# Antenna_Board.net
KiCad netlist of a schematic drawn in EAGLE
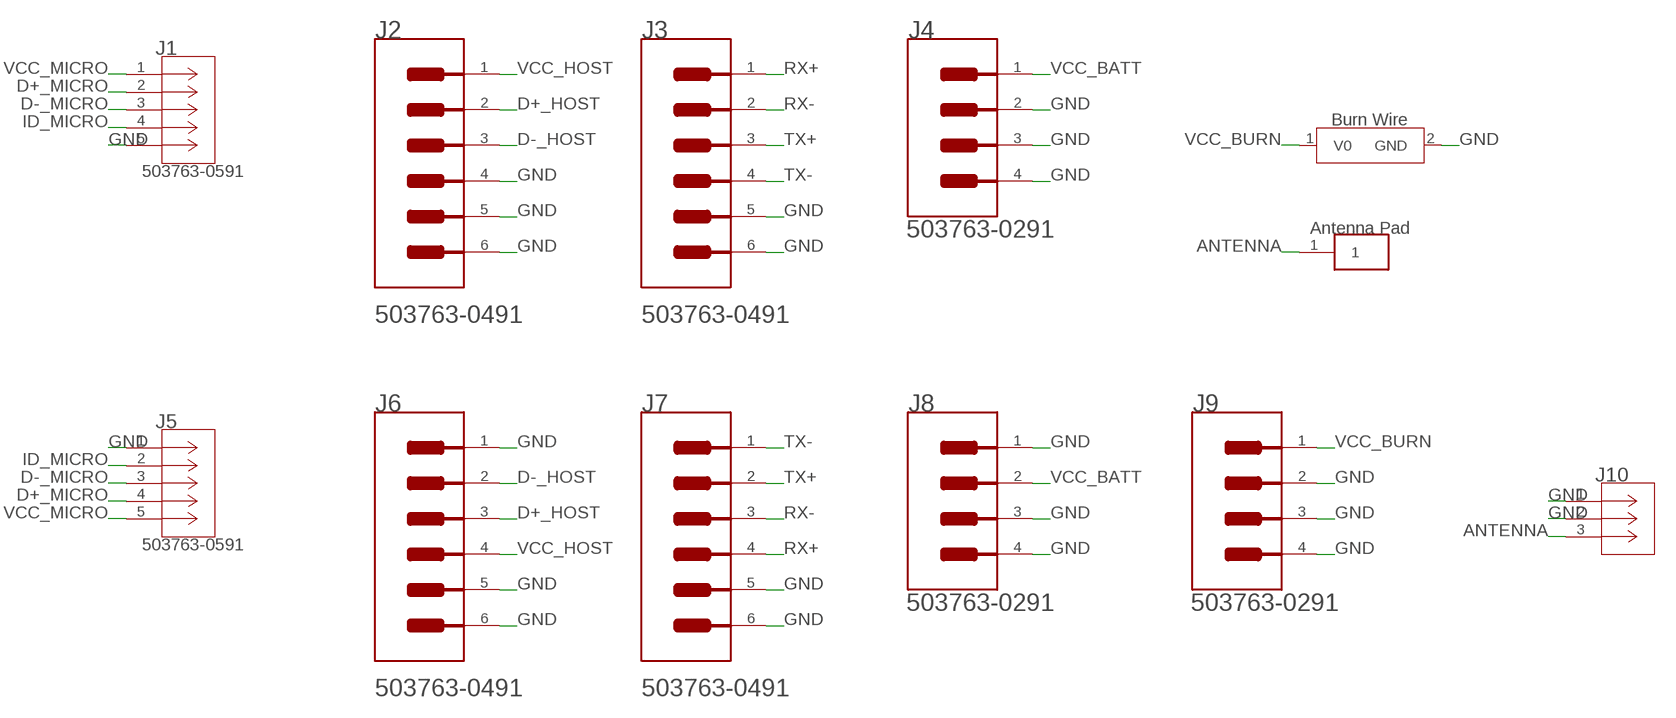
[diagram p0: schematic, sheet 1]

(export (version "E")
  (design (tool "Eeschema 10.0.6"))
  (components
    (comp (ref "J1")
      (value "503763-0591")
      (footprint "eagle-import:CONN_5037630591_MOL")
      (fields (field (name "COPYRIGHT") "Copyright (C) 2018 Accelerated Designs. All rights reserved"))
      (libsource (lib "eagle-import") (part "503763-0591"))
    )
    (comp (ref "J2")
      (value "MOLEX_503763-0491MOLEX_503763-0491_0_0")
      (footprint "eagle-import:MOLEX_503763-0491_0")
      (fields
        (field (name "DIGIKEY_PART_NUMBER") "WM10655CT-ND")
        (field (name "MF") "Molex")
        (field (name "MOUSER_PART_NUMBER") "538-503763-0491")
      )
      (libsource (lib "eagle-import") (part "MOLEX_503763-0491MOLEX_503763-0491_0_0"))
    )
    (comp (ref "J3")
      (value "MOLEX_503763-0491MOLEX_503763-0491_0_0")
      (footprint "eagle-import:MOLEX_503763-0491_0")
      (fields
        (field (name "DIGIKEY_PART_NUMBER") "WM10655CT-ND")
        (field (name "MF") "Molex")
        (field (name "MOUSER_PART_NUMBER") "538-503763-0491")
      )
      (libsource (lib "eagle-import") (part "MOLEX_503763-0491MOLEX_503763-0491_0_0"))
    )
    (comp (ref "J4")
      (value "MOLEX_503763-0291MOLEX_503763-0291_0_0")
      (footprint "eagle-import:MOLEX_503763-0291_0")
      (fields
        (field (name "DIGIKEY_PART_NUMBER") "WM10654CT-ND")
        (field (name "MF") "Molex")
        (field (name "MOUSER_PART_NUMBER") "538-503763-0291")
      )
      (libsource (lib "eagle-import") (part "MOLEX_503763-0291MOLEX_503763-0291_0_0"))
    )
    (comp (ref "J5")
      (value "503763-0591")
      (footprint "eagle-import:CONN_5037630591_MOL")
      (fields (field (name "COPYRIGHT") "Copyright (C) 2018 Accelerated Designs. All rights reserved"))
      (libsource (lib "eagle-import") (part "503763-0591"))
    )
    (comp (ref "J6")
      (value "MOLEX_503763-0491MOLEX_503763-0491_0_0")
      (footprint "eagle-import:MOLEX_503763-0491_0")
      (fields
        (field (name "DIGIKEY_PART_NUMBER") "WM10655CT-ND")
        (field (name "MF") "Molex")
        (field (name "MOUSER_PART_NUMBER") "538-503763-0491")
      )
      (libsource (lib "eagle-import") (part "MOLEX_503763-0491MOLEX_503763-0491_0_0"))
    )
    (comp (ref "J7")
      (value "MOLEX_503763-0491MOLEX_503763-0491_0_0")
      (footprint "eagle-import:MOLEX_503763-0491_0")
      (fields
        (field (name "DIGIKEY_PART_NUMBER") "WM10655CT-ND")
        (field (name "MF") "Molex")
        (field (name "MOUSER_PART_NUMBER") "538-503763-0491")
      )
      (libsource (lib "eagle-import") (part "MOLEX_503763-0491MOLEX_503763-0491_0_0"))
    )
    (comp (ref "J8")
      (value "MOLEX_503763-0291MOLEX_503763-0291_0_0")
      (footprint "eagle-import:MOLEX_503763-0291_0")
      (fields
        (field (name "DIGIKEY_PART_NUMBER") "WM10654CT-ND")
        (field (name "MF") "Molex")
        (field (name "MOUSER_PART_NUMBER") "538-503763-0291")
      )
      (libsource (lib "eagle-import") (part "MOLEX_503763-0291MOLEX_503763-0291_0_0"))
    )
    (comp (ref "J9")
      (value "MOLEX_503763-0291MOLEX_503763-0291_0_0")
      (footprint "eagle-import:MOLEX_503763-0291_0")
      (fields
        (field (name "DIGIKEY_PART_NUMBER") "WM10654CT-ND")
        (field (name "MF") "Molex")
        (field (name "MOUSER_PART_NUMBER") "538-503763-0291")
      )
      (libsource (lib "eagle-import") (part "MOLEX_503763-0291MOLEX_503763-0291_0_0"))
    )
    (comp (ref "J10")
      (value "U.FL-R-SMT-1(01)")
      (footprint "eagle-import:CONN_-SMT-1(01)")
      (fields (field (name "COPYRIGHT") "Copyright (C) 2018 Accelerated Designs. All rights reserved"))
      (libsource (lib "eagle-import") (part "U.FL-R-SMT-1(01)"))
    )
    (comp (ref "U$2")
      (value "ANTENNA_PAD")
      (footprint "eagle-import:ANTENNA_PAD")
      (libsource (lib "eagle-import") (part "ANTENNA_PAD"))
    )
    (comp (ref "U$3")
      (value "BURNWIRE")
      (footprint "eagle-import:BURNWIRE")
      (libsource (lib "eagle-import") (part "BURNWIRE"))
    )
  )
  (nets
    (net (code "1") (name "/ANTENNA") (class "Default")
      (node (ref "J10") (pin "3") (pinfunction "3_3") (pintype "passive"))
      (node (ref "U$2") (pin "1") (pinfunction "1_1") (pintype "bidirectional"))
    )
    (net (code "2") (name "/D+_HOST") (class "Default")
      (node (ref "J2") (pin "2") (pinfunction "2_2") (pintype "passive"))
      (node (ref "J6") (pin "3") (pinfunction "3_3") (pintype "passive"))
    )
    (net (code "3") (name "/D+_MICRO") (class "Default")
      (node (ref "J1") (pin "2") (pinfunction "2_2") (pintype "passive"))
      (node (ref "J5") (pin "4") (pinfunction "4_4") (pintype "passive"))
    )
    (net (code "4") (name "/D-_HOST") (class "Default")
      (node (ref "J2") (pin "3") (pinfunction "3_3") (pintype "passive"))
      (node (ref "J6") (pin "2") (pinfunction "2_2") (pintype "passive"))
    )
    (net (code "5") (name "/D-_MICRO") (class "Default")
      (node (ref "J1") (pin "3") (pinfunction "3_3") (pintype "passive"))
      (node (ref "J5") (pin "3") (pinfunction "3_3") (pintype "passive"))
    )
    (net (code "6") (name "/GND") (class "Default")
      (node (ref "J1") (pin "5") (pinfunction "5_5") (pintype "passive"))
      (node (ref "J10") (pin "1") (pinfunction "1_1") (pintype "passive"))
      (node (ref "J10") (pin "2") (pinfunction "2_2") (pintype "passive"))
      (node (ref "J2") (pin "4") (pinfunction "4_4") (pintype "passive"))
      (node (ref "J2") (pin "5") (pinfunction "MNT_1_5") (pintype "passive"))
      (node (ref "J2") (pin "6") (pinfunction "MNT_2_6") (pintype "passive"))
      (node (ref "J3") (pin "5") (pinfunction "MNT_1_5") (pintype "passive"))
      (node (ref "J3") (pin "6") (pinfunction "MNT_2_6") (pintype "passive"))
      (node (ref "J4") (pin "2") (pinfunction "2_2") (pintype "bidirectional"))
      (node (ref "J4") (pin "3") (pinfunction "MNT_1_3") (pintype "bidirectional"))
      (node (ref "J4") (pin "4") (pinfunction "MNT_2_4") (pintype "bidirectional"))
      (node (ref "J5") (pin "1") (pinfunction "1_1") (pintype "passive"))
      (node (ref "J6") (pin "1") (pinfunction "1_1") (pintype "passive"))
      (node (ref "J6") (pin "5") (pinfunction "MNT_1_5") (pintype "passive"))
      (node (ref "J6") (pin "6") (pinfunction "MNT_2_6") (pintype "passive"))
      (node (ref "J7") (pin "5") (pinfunction "MNT_1_5") (pintype "passive"))
      (node (ref "J7") (pin "6") (pinfunction "MNT_2_6") (pintype "passive"))
      (node (ref "J8") (pin "1") (pinfunction "1_1") (pintype "bidirectional"))
      (node (ref "J8") (pin "3") (pinfunction "MNT_1_3") (pintype "bidirectional"))
      (node (ref "J8") (pin "4") (pinfunction "MNT_2_4") (pintype "bidirectional"))
      (node (ref "J9") (pin "2") (pinfunction "2_2") (pintype "bidirectional"))
      (node (ref "J9") (pin "3") (pinfunction "MNT_1_3") (pintype "bidirectional"))
      (node (ref "J9") (pin "4") (pinfunction "MNT_2_4") (pintype "bidirectional"))
      (node (ref "U$3") (pin "2") (pinfunction "GND_2") (pintype "bidirectional"))
    )
    (net (code "7") (name "/ID_MICRO") (class "Default")
      (node (ref "J1") (pin "4") (pinfunction "4_4") (pintype "passive"))
      (node (ref "J5") (pin "2") (pinfunction "2_2") (pintype "passive"))
    )
    (net (code "8") (name "/RX+") (class "Default")
      (node (ref "J3") (pin "1") (pinfunction "1_1") (pintype "passive"))
      (node (ref "J7") (pin "4") (pinfunction "4_4") (pintype "passive"))
    )
    (net (code "9") (name "/RX-") (class "Default")
      (node (ref "J3") (pin "2") (pinfunction "2_2") (pintype "passive"))
      (node (ref "J7") (pin "3") (pinfunction "3_3") (pintype "passive"))
    )
    (net (code "10") (name "/TX+") (class "Default")
      (node (ref "J3") (pin "3") (pinfunction "3_3") (pintype "passive"))
      (node (ref "J7") (pin "2") (pinfunction "2_2") (pintype "passive"))
    )
    (net (code "11") (name "/TX-") (class "Default")
      (node (ref "J3") (pin "4") (pinfunction "4_4") (pintype "passive"))
      (node (ref "J7") (pin "1") (pinfunction "1_1") (pintype "passive"))
    )
    (net (code "12") (name "/VCC_BATT") (class "Default")
      (node (ref "J4") (pin "1") (pinfunction "1_1") (pintype "bidirectional"))
      (node (ref "J8") (pin "2") (pinfunction "2_2") (pintype "bidirectional"))
    )
    (net (code "13") (name "/VCC_BURN") (class "Default")
      (node (ref "J9") (pin "1") (pinfunction "1_1") (pintype "bidirectional"))
      (node (ref "U$3") (pin "1") (pinfunction "V0_1") (pintype "bidirectional"))
    )
    (net (code "14") (name "/VCC_HOST") (class "Default")
      (node (ref "J2") (pin "1") (pinfunction "1_1") (pintype "passive"))
      (node (ref "J6") (pin "4") (pinfunction "4_4") (pintype "passive"))
    )
    (net (code "15") (name "/VCC_MICRO") (class "Default")
      (node (ref "J1") (pin "1") (pinfunction "1_1") (pintype "passive"))
      (node (ref "J5") (pin "5") (pinfunction "5_5") (pintype "passive"))
    )
  )
)
